# Energy_Monitor.net
KiCad netlist of a schematic drawn in EAGLE
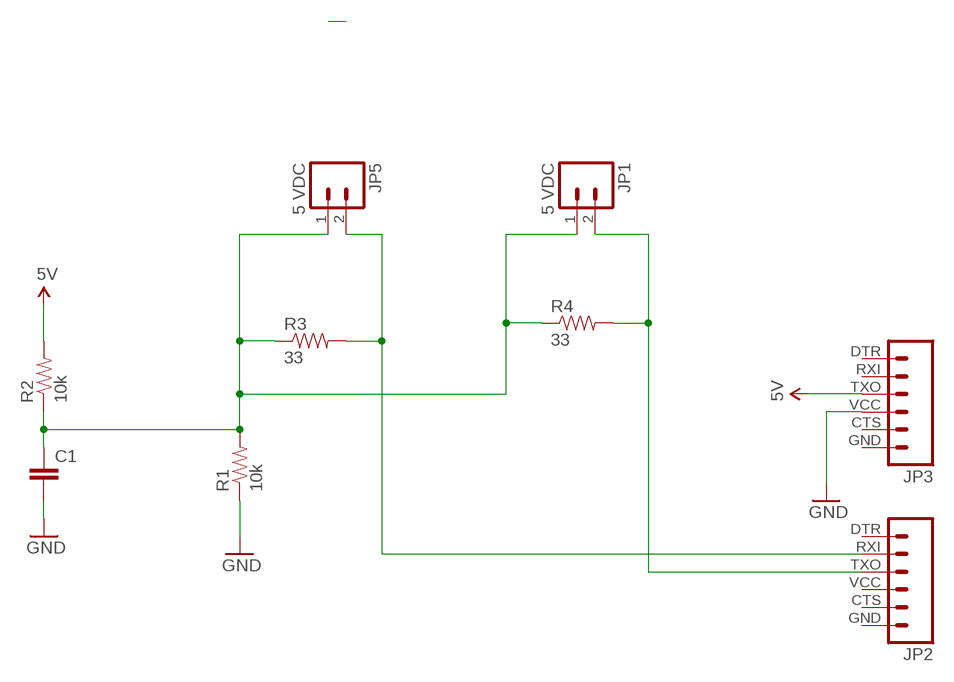
[diagram p0: schematic, sheet 1]

(export (version "E")
  (design (tool "Eeschema 10.0.6"))
  (components
    (comp (ref "C1")
      (value "CAPPTH2")
      (footprint "eagle-import:CAP-PTH-SMALL2")
      (libsource (lib "eagle-import") (part "CAPPTH2"))
    )
    (comp (ref "JP1")
      (value "5 VDC")
      (footprint "eagle-import:SCREWTERMINAL-5MM-2")
      (libsource (lib "eagle-import") (part "M025MM"))
    )
    (comp (ref "JP2")
      (value "M06SIP")
      (footprint "eagle-import:1X06")
      (libsource (lib "eagle-import") (part "M06SIP"))
    )
    (comp (ref "JP3")
      (value "M06SIP")
      (footprint "eagle-import:1X06")
      (libsource (lib "eagle-import") (part "M06SIP"))
    )
    (comp (ref "JP5")
      (value "5 VDC")
      (footprint "eagle-import:SCREWTERMINAL-5MM-2")
      (libsource (lib "eagle-import") (part "M025MM"))
    )
    (comp (ref "R1")
      (value "10k")
      (footprint "eagle-import:AXIAL-0.3")
      (libsource (lib "eagle-import") (part "RESISTORAXIAL-0.3"))
    )
    (comp (ref "R2")
      (value "10k")
      (footprint "eagle-import:AXIAL-0.3")
      (libsource (lib "eagle-import") (part "RESISTORAXIAL-0.3"))
    )
    (comp (ref "R3")
      (value "33")
      (footprint "eagle-import:AXIAL-0.3")
      (libsource (lib "eagle-import") (part "RESISTORAXIAL-0.3"))
    )
    (comp (ref "R4")
      (value "33")
      (footprint "eagle-import:AXIAL-0.3")
      (libsource (lib "eagle-import") (part "RESISTORAXIAL-0.3"))
    )
  )
  (nets
    (net (code "1") (name "5V") (class "Default")
      (node (ref "JP3") (pin "TXO") (pinfunction "3_TXO") (pintype "passive"))
      (node (ref "R2") (pin "P$2") (pinfunction "2_P$2") (pintype "passive"))
    )
    (net (code "2") (name "GND") (class "Default")
      (node (ref "C1") (pin "2") (pinfunction "2_2") (pintype "passive"))
      (node (ref "JP3") (pin "VCC") (pinfunction "4_VCC") (pintype "passive"))
      (node (ref "R1") (pin "P$1") (pinfunction "1_P$1") (pintype "passive"))
    )
    (net (code "3") (name "Net-(JP2-2)") (class "Default")
      (node (ref "JP2") (pin "RXI") (pinfunction "2_RXI") (pintype "passive"))
      (node (ref "JP5") (pin "2") (pinfunction "2_2") (pintype "passive"))
      (node (ref "R3") (pin "P$2") (pinfunction "2_P$2") (pintype "passive"))
    )
    (net (code "4") (name "Net-(JP2-3)") (class "Default")
      (node (ref "JP1") (pin "2") (pinfunction "2_2") (pintype "passive"))
      (node (ref "JP2") (pin "TXO") (pinfunction "3_TXO") (pintype "passive"))
      (node (ref "R4") (pin "P$2") (pinfunction "2_P$2") (pintype "passive"))
    )
    (net (code "5") (name "Net-(R1-2)") (class "Default")
      (node (ref "C1") (pin "1") (pinfunction "1_1") (pintype "passive"))
      (node (ref "JP1") (pin "1") (pinfunction "1_1") (pintype "passive"))
      (node (ref "JP5") (pin "1") (pinfunction "1_1") (pintype "passive"))
      (node (ref "R1") (pin "P$2") (pinfunction "2_P$2") (pintype "passive"))
      (node (ref "R2") (pin "P$1") (pinfunction "1_P$1") (pintype "passive"))
      (node (ref "R3") (pin "P$1") (pinfunction "1_P$1") (pintype "passive"))
      (node (ref "R4") (pin "P$1") (pinfunction "1_P$1") (pintype "passive"))
    )
    (net (code "6") (name "unconnected-(JP2-1-PadDTR)") (class "Default")
      (node (ref "JP2") (pin "DTR") (pinfunction "1_DTR") (pintype "passive"))
    )
    (net (code "7") (name "unconnected-(JP2-4-PadVCC)") (class "Default")
      (node (ref "JP2") (pin "VCC") (pinfunction "4_VCC") (pintype "passive"))
    )
    (net (code "8") (name "unconnected-(JP2-5-PadCTS)") (class "Default")
      (node (ref "JP2") (pin "CTS") (pinfunction "5_CTS") (pintype "passive"))
    )
    (net (code "9") (name "unconnected-(JP2-6-PadGND)") (class "Default")
      (node (ref "JP2") (pin "GND") (pinfunction "6_GND") (pintype "passive"))
    )
    (net (code "10") (name "unconnected-(JP3-1-PadDTR)") (class "Default")
      (node (ref "JP3") (pin "DTR") (pinfunction "1_DTR") (pintype "passive"))
    )
    (net (code "11") (name "unconnected-(JP3-2-PadRXI)") (class "Default")
      (node (ref "JP3") (pin "RXI") (pinfunction "2_RXI") (pintype "passive"))
    )
    (net (code "12") (name "unconnected-(JP3-5-PadCTS)") (class "Default")
      (node (ref "JP3") (pin "CTS") (pinfunction "5_CTS") (pintype "passive"))
    )
    (net (code "13") (name "unconnected-(JP3-6-PadGND)") (class "Default")
      (node (ref "JP3") (pin "GND") (pinfunction "6_GND") (pintype "passive"))
    )
  )
)
